# LC_LPF_PI.net
KiCad netlist of a schematic drawn in Altium Designer
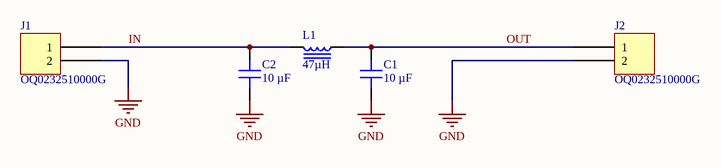
[diagram p0: LC_LPF_PI.SchDoc]

(export (version "E")
  (design (tool "Eeschema 10.0.6"))
  (components
    (comp (ref "C1")
      (value "10 µF")
      (footprint "CAP 0603_1608")
      (description "CAP CER 10UF 10V X5R 0603")
      (fields
        (field (name "PART NUMBER") "MD0603BW106M100NHT-EM")
        (field (name "MANUFACTURER") "Knowles Novacap")
      )
      (libsource (lib "Celestial Altium Library - altium_library") (part "Capacitor"))
    )
    (comp (ref "C2")
      (value "10 µF")
      (footprint "CAP 0603_1608")
      (description "CAP CER 10UF 10V X5R 0603")
      (fields
        (field (name "PART NUMBER") "MD0603BW106M100NHT-EM")
        (field (name "MANUFACTURER") "Knowles Novacap")
      )
      (libsource (lib "Celestial Altium Library - altium_library") (part "Capacitor"))
    )
    (comp (ref "J1")
      (value "OQ0232510000G")
      (footprint "FCI 06-381-2PIN")
      (description "TERM BLOCK HDR 2POS 90DEG 3.81MM")
      (fields (field (name "MANUFACTURER") "Amphenol Anytek"))
      (libsource (lib "") (part "2 Pin_1"))
    )
    (comp (ref "J2")
      (value "OQ0232510000G")
      (footprint "FCI 06-381-2PIN")
      (description "TERM BLOCK HDR 2POS 90DEG 3.81MM")
      (fields (field (name "MANUFACTURER") "Amphenol Anytek"))
      (libsource (lib "Celestial Altium Library - altium_library") (part "2 Pin"))
    )
    (comp (ref "L1")
      (value "47µH")
      (footprint "IND 0603_1608 RF WW")
      (description "INDUCTORPOWER LINE 0603 47H 20%")
      (fields (field (name "PART NUMBER") "L0603B470MPWFT") (field (name "MANUFACTURER") "KEMET"))
      (libsource (lib "Celestial Altium Library - altium_library") (part "Inductor"))
    )
  )
  (nets
    (net (code "1") (name "/IN") (class "Default")
      (node (ref "C2") (pin "2") (pinfunction "2_2") (pintype "passive"))
      (node (ref "J1") (pin "1") (pinfunction "1_1") (pintype "passive"))
      (node (ref "L1") (pin "2") (pinfunction "2_2") (pintype "passive"))
    )
    (net (code "2") (name "/OUT") (class "Default")
      (node (ref "C1") (pin "2") (pinfunction "2_2") (pintype "passive"))
      (node (ref "J2") (pin "1") (pinfunction "1_1") (pintype "passive"))
      (node (ref "L1") (pin "1") (pinfunction "1_1") (pintype "passive"))
    )
    (net (code "3") (name "GND") (class "Default")
      (node (ref "C1") (pin "1") (pinfunction "1_1") (pintype "passive"))
      (node (ref "C2") (pin "1") (pinfunction "1_1") (pintype "passive"))
      (node (ref "J1") (pin "2") (pinfunction "2_2") (pintype "passive"))
      (node (ref "J2") (pin "2") (pinfunction "2_2") (pintype "passive"))
    )
  )
)
